# Carte_MiniPAMI_2024.net
KiCad netlist of a schematic drawn in Altium Designer
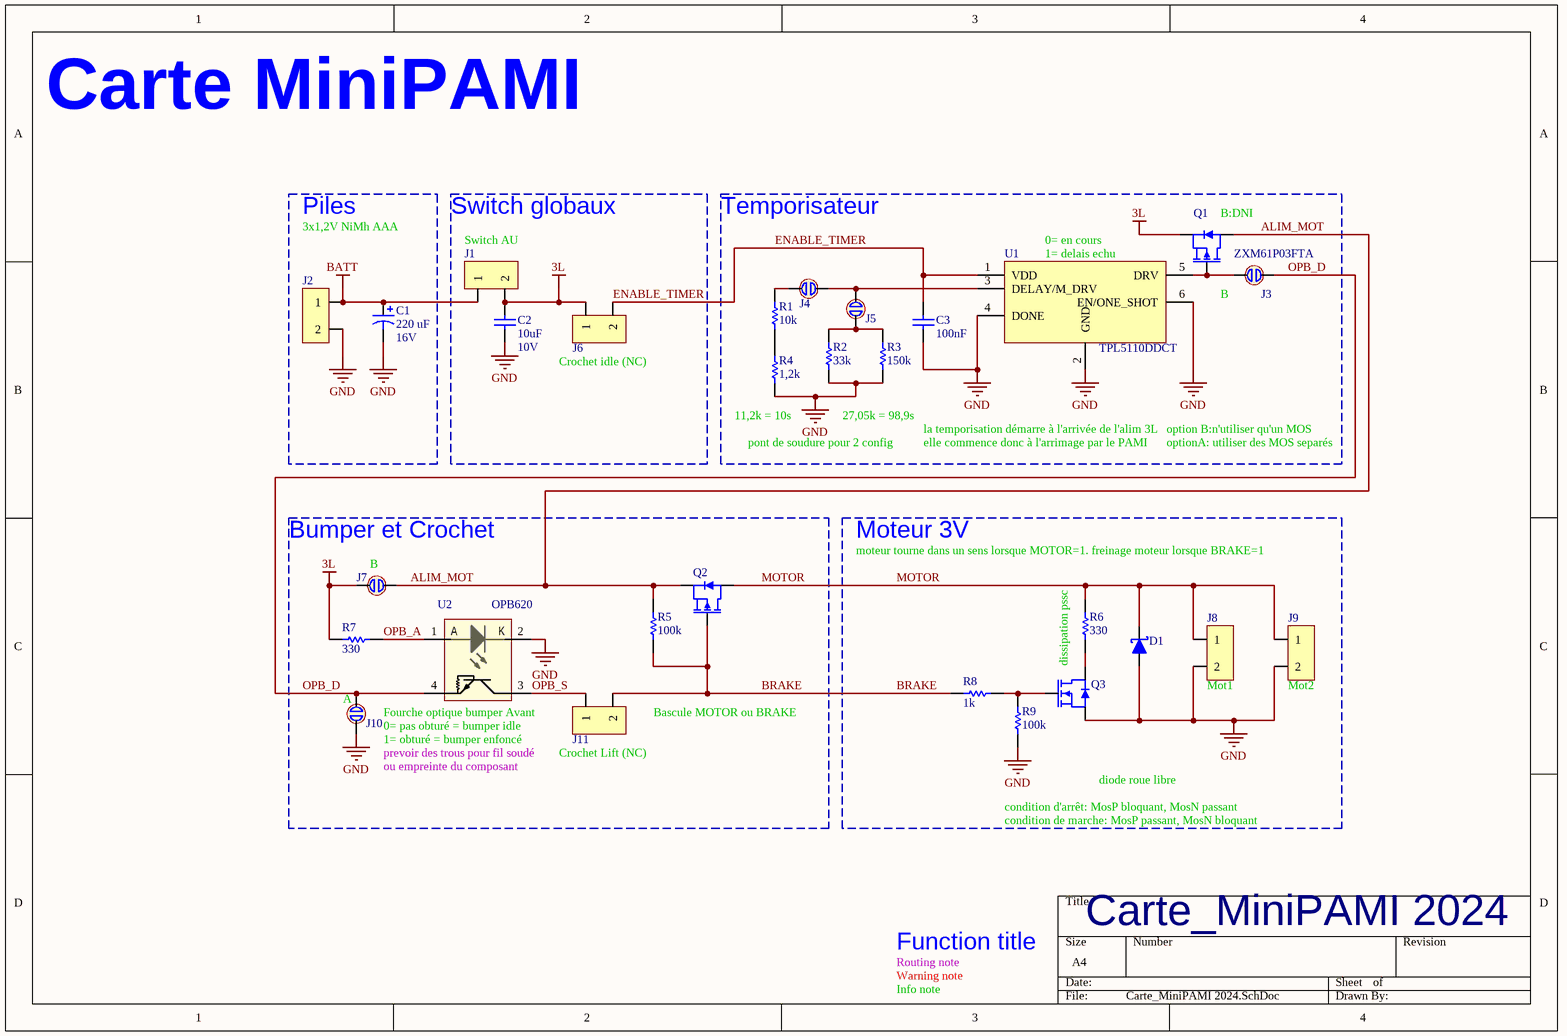
[diagram p0: Carte_MiniPAMI 2024.SchDoc]

(export (version "E")
  (design (tool "Eeschema 10.0.6"))
  (components
    (comp (ref "C1")
      (value "220 uF")
      (footprint "WCAP-ATG8_6.3x11x2.5x0.5")
      (description "CAP Alu 220 UF 20% 16 V")
      (fields
        (field (name "MANUFACTURER") "Wurth Elektronik")
        (field (name "MANUFACTURER PART NUMBER") "860010373010")
        (field (name "RATEDVOLTAGE") "16V")
      )
      (libsource (lib "Condensateur") (part "WCAP-ATG8, 860010373010"))
    )
    (comp (ref "C2")
      (value "10uF")
      (footprint "WCAP-CSGP_0805, 2x1.25x1.25")
      (description "CAP CER 10uF 10V X7R 0805")
      (fields
        (field (name "RATEDVOLTAGE") "10V")
        (field (name "MANUFACTURER") "Wurth Elektronik")
        (field (name "MANUFACTURER PART NUMBER") "885012207026")
      )
      (libsource (lib "Condensateur") (part "WCAP-CSGP, 885012207026"))
    )
    (comp (ref "C3")
      (value "100nF")
      (footprint "WCAP-CSGP_0603, 1.6x0.8x0.8")
      (description "CAP CER 100nF 50V X7R 0603")
      (fields
        (field (name "MANUFACTURER") "Wurth Elektronik")
        (field (name "MANUFACTURER PART NUMBER") "885012206095")
      )
      (libsource (lib "Condensateur") (part "WCAP-CSGP, 885012206095"))
    )
    (comp (ref "D1")
      (value "RBR3MM40ATFTR")
      (footprint "SOD-123FL")
      (description "DIODE SCHOTTKY 40V 3A SOD123-FL")
      (fields (field (name "MANUFACTURER") "ROHM"))
      (libsource (lib "Diode") (part "RBR3MM40ATFTR"))
    )
    (comp (ref "J1")
      (value "22-03-2021")
      (footprint "Conn_22-03-2021")
      (description "CONN HEADER VERT 2POS 2.54MM")
      (fields (field (name "MANUFACTURER") "MOLEX"))
      (libsource (lib "") (part "Conn_22-03-2021_1"))
    )
    (comp (ref "J2")
      (value "22-03-2021")
      (footprint "Conn_22-03-2021")
      (description "CONN HEADER VERT 2POS 2.54MM")
      (fields (field (name "MANUFACTURER") "MOLEX"))
      (libsource (lib "") (part "Conn_22-03-2021_3"))
    )
    (comp (ref "J3")
      (value "open")
      (footprint "CAVALIER")
      (description "Cavalier soudure \"ouvert\", pastille fendue 1.2mm")
      (libsource (lib "Divers") (part "CAVALIER_DOT"))
    )
    (comp (ref "J4")
      (value "open")
      (footprint "CAVALIER")
      (description "Cavalier soudure \"ouvert\", pastille fendue 1.2mm")
      (libsource (lib "Divers") (part "CAVALIER_DOT"))
    )
    (comp (ref "J5")
      (value "open")
      (footprint "CAVALIER")
      (description "Cavalier soudure \"ouvert\", pastille fendue 1.2mm")
      (libsource (lib "Divers") (part "CAVALIER_DOT"))
    )
    (comp (ref "J6")
      (value "22-03-2021")
      (footprint "Conn_22-03-2021")
      (description "CONN HEADER VERT 2POS 2.54MM")
      (fields (field (name "MANUFACTURER") "MOLEX"))
      (libsource (lib "Connecteurs") (part "Conn_22-03-2021"))
    )
    (comp (ref "J7")
      (value "open")
      (footprint "CAVALIER")
      (description "Cavalier soudure \"ouvert\", pastille fendue 1.2mm")
      (libsource (lib "Divers") (part "CAVALIER_DOT"))
    )
    (comp (ref "J8")
      (value "22-03-2021")
      (footprint "Conn_22-03-2021")
      (description "CONN HEADER VERT 2POS 2.54MM")
      (fields (field (name "MANUFACTURER") "MOLEX"))
      (libsource (lib "") (part "Conn_22-03-2021_2"))
    )
    (comp (ref "J9")
      (value "22-03-2021")
      (footprint "Conn_22-03-2021")
      (description "CONN HEADER VERT 2POS 2.54MM")
      (fields (field (name "MANUFACTURER") "MOLEX"))
      (libsource (lib "") (part "Conn_22-03-2021_2"))
    )
    (comp (ref "J10")
      (value "open")
      (footprint "CAVALIER")
      (description "Cavalier soudure \"ouvert\", pastille fendue 1.2mm")
      (libsource (lib "Divers") (part "CAVALIER_DOT"))
    )
    (comp (ref "J11")
      (value "22-03-2021")
      (footprint "Conn_22-03-2021")
      (description "CONN HEADER VERT 2POS 2.54MM")
      (fields (field (name "MANUFACTURER") "MOLEX"))
      (libsource (lib "Connecteurs") (part "Conn_22-03-2021"))
    )
    (comp (ref "Q1")
      (value "ZXM61P03FTA")
      (footprint "SOT-23")
      (description "MOSFET P-CH 30V 1.1A SOT23-3")
      (fields (field (name "MANUFACTURER") "Diodes Incorporated"))
      (libsource (lib "Transistors") (part "ZXM61P03FTA"))
    )
    (comp (ref "Q2")
      (value "ZXM61P03FTA")
      (footprint "SOT-23")
      (description "MOSFET P-CH 30V 1.1A SOT23-3")
      (fields (field (name "MANUFACTURER") "Diodes Incorporated"))
      (libsource (lib "Transistors") (part "ZXM61P03FTA"))
    )
    (comp (ref "Q3")
      (value "IRLML0040TRPBF")
      (footprint "SOT-23")
      (description "MOSFET N 40V 3.6A SOT23")
      (fields (field (name "MANUFACTURER") "INTERNATIONAL RECTIFIER"))
      (libsource (lib "Transistors") (part "IRLML0040"))
    )
    (comp (ref "R1")
      (value "10k")
      (footprint "RESC1608X06N")
      (description "RES SMD 10K OHM 1% 1/10W 0603")
      (fields
        (field (name "MANUFACTURER") "Yageo")
        (field (name "MANUFACTURER PART NUMBER") "RC0603FR-0710KL")
      )
      (libsource (lib "Resistance") (part "RC0603FR-0710KL"))
    )
    (comp (ref "R2")
      (value "33k")
      (footprint "RESC1608X06N")
      (description "RES SMD 33K OHM 1% 1/10W 0603")
      (fields (field (name "MANUFACTURER") "Yageo") (field (name "POWER") "100mW"))
      (libsource (lib "Resistance") (part "RC0603FR-0710KL"))
    )
    (comp (ref "R3")
      (value "150k")
      (footprint "RESC1608X06N")
      (description "RES SMD 150K OHM 1% 1/10W 0603")
      (fields (field (name "MANUFACTURER") "Yageo") (field (name "POWER") "100mW"))
      (libsource (lib "Resistance") (part "RC0603FR-07100KL"))
    )
    (comp (ref "R4")
      (value "1,2k")
      (footprint "RESC1608X06N")
      (description "RES SMD 1,2K OHM 1% 1/10W 0603")
      (fields (field (name "MANUFACTURER") "Yageo") (field (name "POWER") "100mW"))
      (libsource (lib "Resistance") (part "RC0603FR-071KL"))
    )
    (comp (ref "R5")
      (value "100k")
      (footprint "RESC1608X06N")
      (description "RES SMD 100K OHM 1% 1/10W 0603")
      (fields
        (field (name "MANUFACTURER") "Yageo")
        (field (name "MANUFACTURER PART NUMBER") "RC0603FR-07100KL")
      )
      (libsource (lib "Resistance") (part "RC0603FR-07100KL"))
    )
    (comp (ref "R6")
      (value "330")
      (footprint "RESC1608X06N")
      (description "RES SMD 330 OHM 1% 1/10W 0603")
      (fields
        (field (name "MANUFACTURER") "Yageo")
        (field (name "MANUFACTURER PART NUMBER") "RC0603FR-07330RL")
      )
      (libsource (lib "Resistance") (part "RC0603FR-07330RL"))
    )
    (comp (ref "R7")
      (value "330")
      (footprint "RESC1608X06N")
      (description "RES SMD 330 OHM 1% 1/10W 0603")
      (fields
        (field (name "MANUFACTURER") "Yageo")
        (field (name "MANUFACTURER PART NUMBER") "RC0603FR-07330RL")
      )
      (libsource (lib "Resistance") (part "RC0603FR-07330RL"))
    )
    (comp (ref "R8")
      (value "1k")
      (footprint "RESC1608X06N")
      (description "RES SMD 1K OHM 1% 1/10W 0603")
      (fields
        (field (name "MANUFACTURER") "Yageo")
        (field (name "MANUFACTURER PART NUMBER") "RC0603FR-071KL")
      )
      (libsource (lib "Resistance") (part "RC0603FR-071KL"))
    )
    (comp (ref "R9")
      (value "100k")
      (footprint "RESC1608X06N")
      (description "RES SMD 100K OHM 1% 1/10W 0603")
      (fields
        (field (name "MANUFACTURER") "Yageo")
        (field (name "MANUFACTURER PART NUMBER") "RC0603FR-07100KL")
      )
      (libsource (lib "Resistance") (part "RC0603FR-07100KL"))
    )
    (comp (ref "U1")
      (value "TPL5110DDCT")
      (footprint "SOT23_95P280X145-6N")
      (description "IC OSC PROG TIMER TSOT23-6")
      (fields (field (name "MANUFACTURER") "TEXAS INSTRUMENTS"))
      (libsource (lib "CI") (part "TPL5110DDCT"))
    )
    (comp (ref "U2")
      (value "OPB620")
      (footprint "OPB620")
      (description "SENSOR OPT SLOT TRANS W/RES PCB")
      (fields (field (name "MANUFACTURER") "TT ELECTRONICS"))
      (libsource (lib "Opto") (part "OPB620"))
    )
  )
  (nets
    (net (code "1") (name "/ALIM_MOT") (class "Default")
      (node (ref "J7") (pin "2") (pinfunction "2_2") (pintype "passive"))
      (node (ref "Q1") (pin "3") (pinfunction "D_3") (pintype "passive"))
      (node (ref "Q2") (pin "2") (pinfunction "S_2") (pintype "passive"))
      (node (ref "R5") (pin "2") (pinfunction "2_2") (pintype "passive"))
    )
    (net (code "2") (name "/BRAKE") (class "Default")
      (node (ref "J11") (pin "2") (pinfunction "2_2") (pintype "passive"))
      (node (ref "Q2") (pin "1") (pinfunction "G_1") (pintype "passive"))
      (node (ref "R5") (pin "1") (pinfunction "1_1") (pintype "passive"))
      (node (ref "R8") (pin "2") (pinfunction "2_2") (pintype "passive"))
    )
    (net (code "3") (name "/ENABLE_TIMER") (class "Default")
      (node (ref "C3") (pin "1") (pinfunction "1_1") (pintype "passive"))
      (node (ref "J6") (pin "2") (pinfunction "2_2") (pintype "passive"))
      (node (ref "U1") (pin "1") (pinfunction "VDD_1") (pintype "passive"))
    )
    (net (code "4") (name "/MOTOR") (class "Default")
      (node (ref "D1") (pin "2") (pintype "passive"))
      (node (ref "J8") (pin "1") (pinfunction "1_1") (pintype "passive"))
      (node (ref "J9") (pin "1") (pinfunction "1_1") (pintype "passive"))
      (node (ref "Q2") (pin "3") (pinfunction "D_3") (pintype "passive"))
      (node (ref "R6") (pin "2") (pinfunction "2_2") (pintype "passive"))
    )
    (net (code "5") (name "/OPB_A") (class "Default")
      (node (ref "R7") (pin "2") (pinfunction "2_2") (pintype "passive"))
      (node (ref "U2") (pin "1") (pinfunction "LED_A_1") (pintype "passive"))
    )
    (net (code "6") (name "/OPB_D") (class "Default")
      (node (ref "J10") (pin "2") (pinfunction "2_2") (pintype "passive"))
      (node (ref "J3") (pin "2") (pinfunction "2_2") (pintype "passive"))
      (node (ref "U2") (pin "4") (pinfunction "NPN_E_4") (pintype "passive"))
    )
    (net (code "7") (name "/OPB_S") (class "Default")
      (node (ref "J11") (pin "1") (pinfunction "1_1") (pintype "passive"))
      (node (ref "U2") (pin "3") (pinfunction "NPN_C_3") (pintype "passive"))
    )
    (net (code "8") (name "3L") (class "Default")
      (node (ref "C2") (pin "1") (pinfunction "1_1") (pintype "passive"))
      (node (ref "J1") (pin "2") (pinfunction "2_2") (pintype "passive"))
      (node (ref "J6") (pin "1") (pinfunction "1_1") (pintype "passive"))
      (node (ref "J7") (pin "1") (pinfunction "1_1") (pintype "passive"))
      (node (ref "Q1") (pin "2") (pinfunction "S_2") (pintype "passive"))
      (node (ref "R7") (pin "1") (pinfunction "1_1") (pintype "passive"))
    )
    (net (code "9") (name "BATT") (class "Default")
      (node (ref "C1") (pin "1") (pinfunction "1_1") (pintype "passive"))
      (node (ref "J1") (pin "1") (pinfunction "1_1") (pintype "passive"))
      (node (ref "J2") (pin "1") (pinfunction "1_1") (pintype "passive"))
    )
    (net (code "10") (name "GND") (class "Default")
      (node (ref "C1") (pin "2") (pinfunction "2_2") (pintype "passive"))
      (node (ref "C2") (pin "2") (pinfunction "2_2") (pintype "passive"))
      (node (ref "C3") (pin "2") (pinfunction "2_2") (pintype "passive"))
      (node (ref "D1") (pin "1") (pintype "passive"))
      (node (ref "J10") (pin "1") (pinfunction "1_1") (pintype "passive"))
      (node (ref "J2") (pin "2") (pinfunction "2_2") (pintype "passive"))
      (node (ref "J8") (pin "2") (pinfunction "2_2") (pintype "passive"))
      (node (ref "J9") (pin "2") (pinfunction "2_2") (pintype "passive"))
      (node (ref "Q3") (pin "2") (pinfunction "S_2") (pintype "passive"))
      (node (ref "R2") (pin "2") (pinfunction "2_2") (pintype "passive"))
      (node (ref "R3") (pin "2") (pinfunction "2_2") (pintype "passive"))
      (node (ref "R4") (pin "1") (pinfunction "1_1") (pintype "passive"))
      (node (ref "R9") (pin "1") (pinfunction "1_1") (pintype "passive"))
      (node (ref "U1") (pin "2") (pinfunction "GND_2") (pintype "passive"))
      (node (ref "U1") (pin "4") (pinfunction "DONE_4") (pintype "passive"))
      (node (ref "U1") (pin "6") (pinfunction "EN/ONE_SHOT_6") (pintype "passive"))
      (node (ref "U2") (pin "2") (pinfunction "LED_K_2") (pintype "passive"))
    )
    (net (code "11") (name "Net-(J4-Pad1)") (class "Default")
      (node (ref "J4") (pin "1") (pinfunction "1_1") (pintype "passive"))
      (node (ref "R1") (pin "2") (pinfunction "2_2") (pintype "passive"))
    )
    (net (code "12") (name "Net-(J5-Pad1)") (class "Default")
      (node (ref "J5") (pin "1") (pinfunction "1_1") (pintype "passive"))
      (node (ref "R2") (pin "1") (pinfunction "1_1") (pintype "passive"))
      (node (ref "R3") (pin "1") (pinfunction "1_1") (pintype "passive"))
    )
    (net (code "13") (name "Net-(Q1-G)") (class "Default")
      (node (ref "J3") (pin "1") (pinfunction "1_1") (pintype "passive"))
      (node (ref "Q1") (pin "1") (pinfunction "G_1") (pintype "passive"))
      (node (ref "U1") (pin "5") (pinfunction "DRV_5") (pintype "passive"))
    )
    (net (code "14") (name "Net-(Q3-D)") (class "Default")
      (node (ref "Q3") (pin "3") (pinfunction "D_3") (pintype "passive"))
      (node (ref "R6") (pin "1") (pinfunction "1_1") (pintype "passive"))
    )
    (net (code "15") (name "Net-(Q3-G)") (class "Default")
      (node (ref "Q3") (pin "1") (pinfunction "G_1") (pintype "passive"))
      (node (ref "R8") (pin "1") (pinfunction "1_1") (pintype "passive"))
      (node (ref "R9") (pin "2") (pinfunction "2_2") (pintype "passive"))
    )
    (net (code "16") (name "Net-(R1-Pad1)") (class "Default")
      (node (ref "R1") (pin "1") (pinfunction "1_1") (pintype "passive"))
      (node (ref "R4") (pin "2") (pinfunction "2_2") (pintype "passive"))
    )
    (net (code "17") (name "Net-(U1-DELAY{slash}M_DRV)") (class "Default")
      (node (ref "J4") (pin "2") (pinfunction "2_2") (pintype "passive"))
      (node (ref "J5") (pin "2") (pinfunction "2_2") (pintype "passive"))
      (node (ref "U1") (pin "3") (pinfunction "DELAY/M_DRV_3") (pintype "passive"))
    )
  )
)
